# Top.net
KiCad netlist of a schematic drawn in Altium Designer
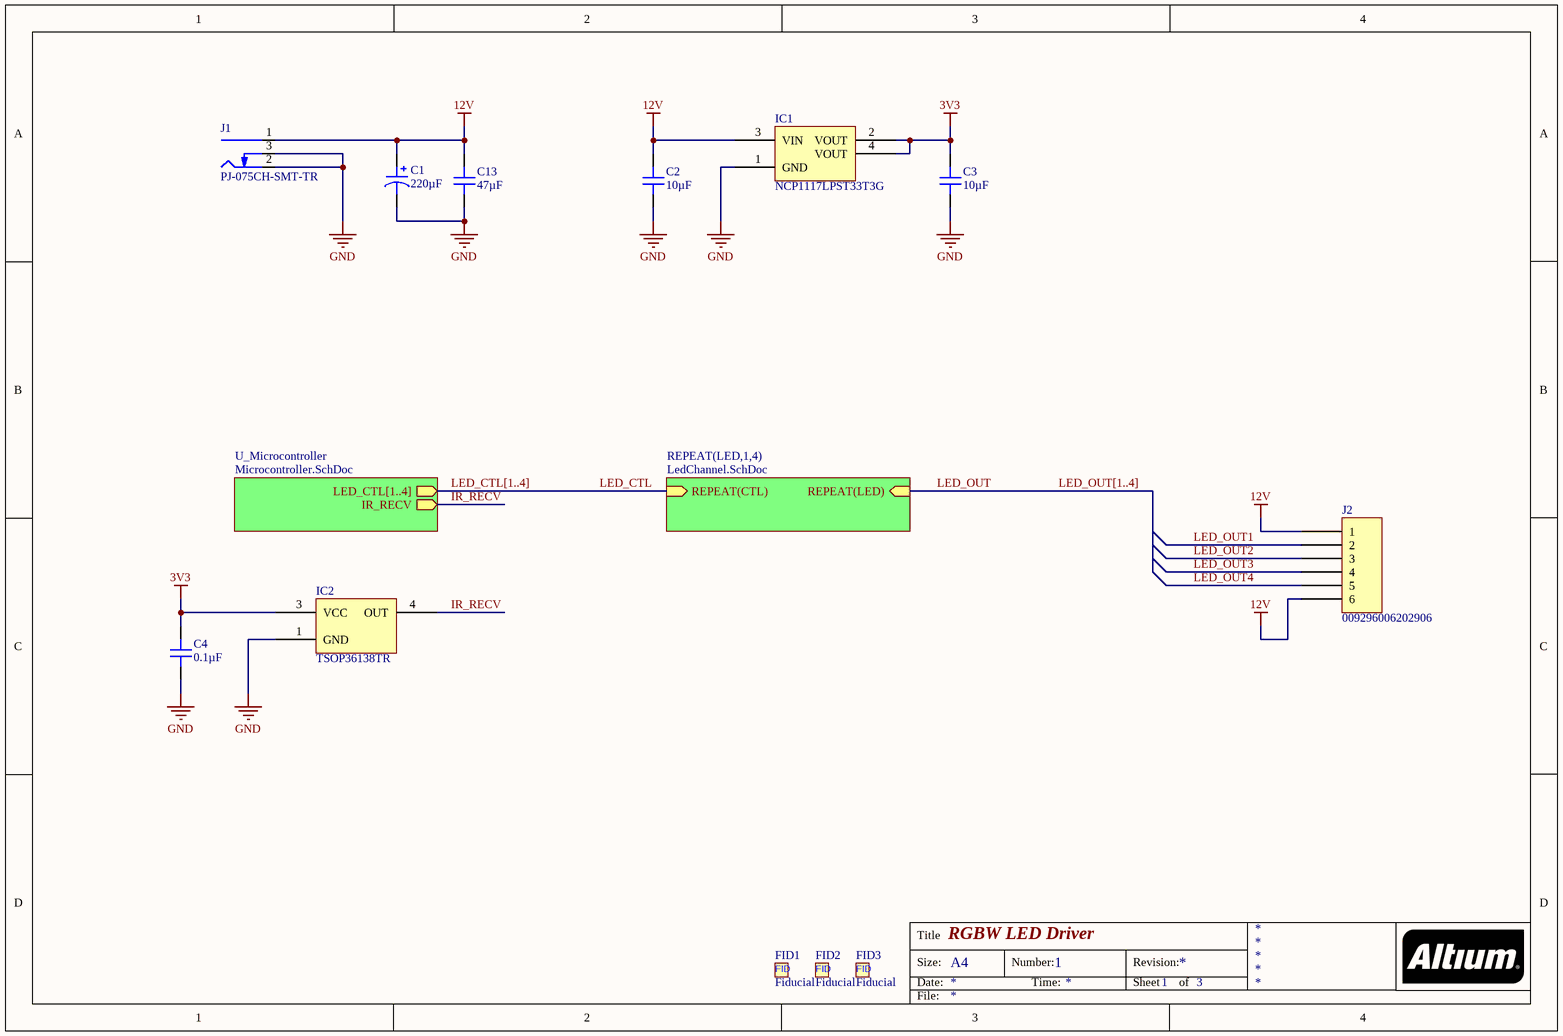
[diagram p0: Top.SchDoc]

(export (version "E")
  (design (tool "Eeschema 10.0.6"))
  (components
    (comp (ref "C1")
      (value "220µF")
      (footprint "CAP ALSMD 8.3MM H10.5MM")
      (description "CAP ALUM 220UF 20% 25V SMD")
      (fields (field (name "PART NUMBER") "UUX1E221MNL6GS") (field (name "MANUFACTURER") "Nichicon"))
      (libsource (lib "Celestial Altium Library - altium_library") (part "Polarised Capacitor"))
    )
    (comp (ref "C2")
      (value "10µF")
      (footprint "CAP 1206_3216 - 1.8MM")
      (description "CAP CER 10UF 25V X5R 1206")
      (fields
        (field (name "PART NUMBER") "CL31A106KAHNNNE")
        (field (name "MANUFACTURER") "Samsung Electro-Mechanics")
      )
      (libsource (lib "Celestial Altium Library - altium_library") (part "Capacitor"))
    )
    (comp (ref "C3")
      (value "10µF")
      (footprint "CAP 1206_3216 - 1.8MM")
      (description "CAP CER 10UF 25V X5R 1206")
      (fields
        (field (name "PART NUMBER") "CL31A106KAHNNNE")
        (field (name "MANUFACTURER") "Samsung Electro-Mechanics")
      )
      (libsource (lib "Celestial Altium Library - altium_library") (part "Capacitor"))
    )
    (comp (ref "C4")
      (value "0.1µF")
      (footprint "CAP 0603_1608")
      (description "CAP CER 0.1UF 16V X7R 0603")
      (fields (field (name "PART NUMBER") "CS0603KRX7R7BB104") (field (name "MANUFACTURER") "Yageo"))
      (libsource (lib "Celestial Altium Library - altium_library") (part "Capacitor"))
    )
    (comp (ref "C13")
      (value "47µF")
      (footprint "CAP 1206_3216 - 1.8MM")
      (description "CAP CER 47UF 25V X5R 1206")
      (fields
        (field (name "PART NUMBER") "GRM31CR61E476ME44L")
        (field (name "MANUFACTURER") "Murata Electronics")
      )
      (libsource (lib "Celestial Altium Library - altium_library") (part "Capacitor"))
    )
    (comp (ref "FID1")
      (value "Fiducial")
      (footprint "Fiducial-1mm")
      (libsource (lib "CelestialUseful") (part "Fiducial"))
    )
    (comp (ref "FID2")
      (value "Fiducial")
      (footprint "Fiducial-1mm")
      (libsource (lib "CelestialUseful") (part "Fiducial"))
    )
    (comp (ref "FID3")
      (value "Fiducial")
      (footprint "Fiducial-1mm")
      (libsource (lib "CelestialUseful") (part "Fiducial"))
    )
    (comp (ref "IC1")
      (value "NCP1117LPST33T3G")
      (footprint "ON SEMI SOT-223 ST(318H)")
      (description "IC REG LINEAR 3.3V 1A SOT223")
      (fields (field (name "MANUFACTURER") "ON Semiconductor"))
      (libsource (lib "Celestial Altium Library - altium_library") (part "ON Semi NCP1117"))
    )
    (comp (ref "IC2")
      (value "TSOP36138TR")
      (footprint "VISHAY TSOP36X-TR")
      (description "SENSOR REMOTE REC 38.0KHZ 45M")
      (fields (field (name "MANUFACTURER") "Vishay Semiconductor Opto Division"))
      (libsource (lib "Celestial Altium Library - altium_library") (part "Vishay TSOP36x"))
    )
    (comp (ref "J1")
      (value "PJ-075CH-SMT-TR")
      (footprint "CUI PJ-075-SMT")
      (description "CONN PWR JACK 1X3.4MM SOLDER")
      (fields (field (name "MANUFACTURER") "CUI Devices"))
      (libsource (lib "Celestial Altium Library - altium_library") (part "Barrel Connector"))
    )
    (comp (ref "J2")
      (value "009296006202906")
      (footprint "AVX 9296006202806")
      (description "CONN WIRE POKE-IN 6POS SMD RA")
      (fields (field (name "MANUFACTURER") "AVX Corporation"))
      (libsource (lib "Celestial Altium Library - altium_library") (part "6 Pin"))
    )
  )
  (nets
    (net (code "5") (name "/IR_RECV") (class "Default")
      (node (ref "IC2") (pin "4") (pinfunction "OUT_4") (pintype "passive"))
    )
    (net (code "9") (name "/LED_OUT1") (class "Default")
      (node (ref "J2") (pin "2") (pinfunction "2_2") (pintype "passive"))
    )
    (net (code "10") (name "/LED_OUT2") (class "Default")
      (node (ref "J2") (pin "3") (pinfunction "3_3") (pintype "passive"))
    )
    (net (code "11") (name "/LED_OUT3") (class "Default")
      (node (ref "J2") (pin "4") (pinfunction "4_4") (pintype "passive"))
    )
    (net (code "12") (name "/LED_OUT4") (class "Default")
      (node (ref "J2") (pin "5") (pinfunction "5_5") (pintype "passive"))
    )
    (net (code "14") (name "3V3") (class "Default")
      (node (ref "C3") (pin "2") (pinfunction "2_2") (pintype "passive"))
      (node (ref "C4") (pin "2") (pinfunction "2_2") (pintype "passive"))
      (node (ref "IC1") (pin "2") (pinfunction "VOUT_2") (pintype "passive"))
      (node (ref "IC1") (pin "4") (pinfunction "VOUT_4") (pintype "passive"))
      (node (ref "IC2") (pin "3") (pinfunction "VCC_3") (pintype "passive"))
    )
    (net (code "15") (name "12V") (class "Default")
      (node (ref "C1") (pin "1") (pinfunction "1_1") (pintype "passive"))
      (node (ref "C13") (pin "2") (pinfunction "2_2") (pintype "passive"))
      (node (ref "C2") (pin "2") (pinfunction "2_2") (pintype "passive"))
      (node (ref "IC1") (pin "3") (pinfunction "VIN_3") (pintype "passive"))
      (node (ref "J1") (pin "1") (pinfunction "Centre_1") (pintype "passive"))
      (node (ref "J2") (pin "1") (pinfunction "1_1") (pintype "passive"))
      (node (ref "J2") (pin "6") (pinfunction "6_6") (pintype "passive"))
    )
    (net (code "16") (name "GND") (class "Default")
      (node (ref "C1") (pin "2") (pinfunction "2_2") (pintype "passive"))
      (node (ref "C13") (pin "1") (pinfunction "1_1") (pintype "passive"))
      (node (ref "C2") (pin "1") (pinfunction "1_1") (pintype "passive"))
      (node (ref "C3") (pin "1") (pinfunction "1_1") (pintype "passive"))
      (node (ref "C4") (pin "1") (pinfunction "1_1") (pintype "passive"))
      (node (ref "IC1") (pin "1") (pinfunction "GND_1") (pintype "passive"))
      (node (ref "IC2") (pin "1") (pinfunction "GND_1") (pintype "passive"))
      (node (ref "J1") (pin "2") (pinfunction "Outer_2") (pintype "passive"))
      (node (ref "J1") (pin "3") (pinfunction "SW_3") (pintype "passive"))
    )
  )
)
